# BabyPukeko.net
KiCad netlist of a schematic drawn in Altium Designer
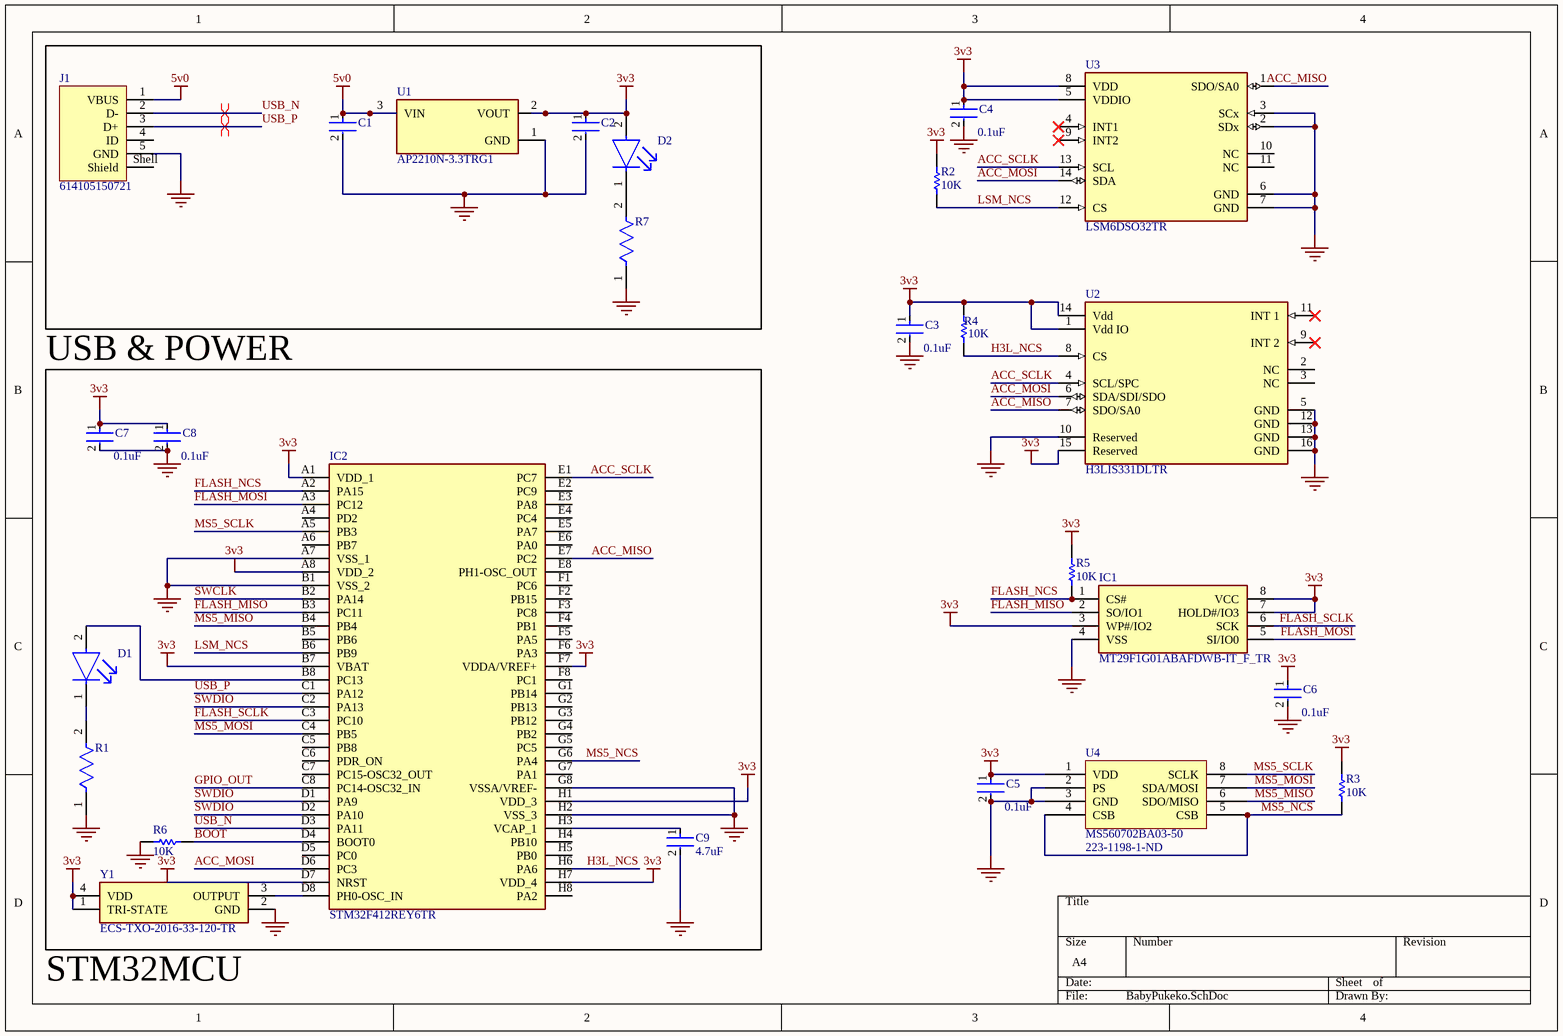
[diagram p0: BabyPukeko.SchDoc]

(export (version "E")
  (design (tool "Eeschema 10.0.6"))
  (components
    (comp (ref "C1")
      (value "C0402C105K8PACTU")
      (footprint "FP-C0402C105K8PACTU-MFG")
      (description "CAP CER 1UF 10V X5R 0402")
      (fields (field (name "VOLTAGE") "10V") (field (name "TOLERANCE") "10%"))
      (libsource (lib "Altium Content Vault") (part "11868f565c42a9108669ba33697ecf6"))
    )
    (comp (ref "C2")
      (value "C0402C105K8PACTU")
      (footprint "FP-C0402C105K8PACTU-MFG")
      (description "CAP CER 1UF 10V X5R 0402")
      (fields (field (name "VOLTAGE") "10V") (field (name "TOLERANCE") "10%"))
      (libsource (lib "Altium Content Vault") (part "11868f565c42a9108669ba33697ecf6"))
    )
    (comp (ref "C3")
      (value "0.1uF")
      (footprint "FP-C0402-BB-MFG")
      (description "CAP CER 0.1UF 10V X5R 0402")
      (fields (field (name "MANUFACTURER") "Kemet") (field (name "TOLERANCE") "0.1"))
      (libsource (lib "Altium Content Vault") (part "b4654b650e69147ec39a6b967a45e02"))
    )
    (comp (ref "C4")
      (value "0.1uF")
      (footprint "FP-C0402-BB-MFG")
      (description "CAP CER 0.1UF 10V X5R 0402")
      (fields (field (name "MANUFACTURER") "Kemet") (field (name "TOLERANCE") "0.1"))
      (libsource (lib "Altium Content Vault") (part "b4654b650e69147ec39a6b967a45e02"))
    )
    (comp (ref "C5")
      (value "0.1uF")
      (footprint "FP-C0402-BB-MFG")
      (description "CAP CER 0.1UF 10V X5R 0402")
      (fields (field (name "MANUFACTURER") "Kemet") (field (name "TOLERANCE") "0.1"))
      (libsource (lib "Altium Content Vault") (part "b4654b650e69147ec39a6b967a45e02"))
    )
    (comp (ref "C6")
      (value "0.1uF")
      (footprint "FP-C0402-BB-MFG")
      (description "CAP CER 0.1UF 10V X5R 0402")
      (fields (field (name "MANUFACTURER") "Kemet") (field (name "TOLERANCE") "0.1"))
      (libsource (lib "Altium Content Vault") (part "b4654b650e69147ec39a6b967a45e02"))
    )
    (comp (ref "C7")
      (value "0.1uF")
      (footprint "FP-C0402-BB-MFG")
      (description "CAP CER 0.1UF 10V X5R 0402")
      (fields (field (name "MANUFACTURER") "Kemet") (field (name "TOLERANCE") "0.1"))
      (libsource (lib "Altium Content Vault") (part "b4654b650e69147ec39a6b967a45e02"))
    )
    (comp (ref "C8")
      (value "0.1uF")
      (footprint "FP-C0402-BB-MFG")
      (description "CAP CER 0.1UF 10V X5R 0402")
      (fields (field (name "MANUFACTURER") "Kemet") (field (name "TOLERANCE") "0.1"))
      (libsource (lib "Altium Content Vault") (part "b4654b650e69147ec39a6b967a45e02"))
    )
    (comp (ref "C9")
      (value "4.7uF")
      (footprint "FP-C1005-050-0_15-MFG")
      (description "CAP CER 4.7UF 10V X5R 0402")
      (fields (field (name "TOLERANCE") "10%"))
      (libsource (lib "Altium Content Vault") (part "b4654b650e69147ec39a6b967a45e02"))
    )
    (comp (ref "D1")
      (value "APHHS1005CGCK")
      (footprint "FP-APHHS1005CGCK-MFG")
      (description "LED GREEN CLEAR CHIP SMD")
      (libsource (lib "Altium Content Vault") (part "8706943c75ba83719d021d2fdc84c58"))
    )
    (comp (ref "D2")
      (value "APHHS1005CGCK")
      (footprint "FP-APHHS1005CGCK-MFG")
      (description "LED GREEN CLEAR CHIP SMD")
      (libsource (lib "Altium Content Vault") (part "8706943c75ba83719d021d2fdc84c58"))
    )
    (comp (ref "IC1")
      (value "MT29F1G01ABAFDWB-IT_F_TR")
      (footprint "SamacSys:SON127P800X600X65-8N")
      (description "Integrated Circuit")
      (fields
        (field (name "MANUFACTURER_PART_NUMBER") "MT29F1G01ABAFDWB-IT:F TR")
        (field (name "MOUSER PART NUMBER") "340-319941-REEL")
      )
      (libsource (lib "*") (part "MT29F1G01ABAFDWB-IT_F_TR"))
    )
    (comp (ref "IC2")
      (value "STM32F412REY6TR")
      (footprint "SamacSys:BGA64C40P8X8_362X365X58")
      (description "Integrated Circuit")
      (fields (field (name "MOUSER PART NUMBER") "511-STM32F412REY6TR"))
      (libsource (lib "*") (part "STM32F412REY6TR"))
    )
    (comp (ref "J1")
      (value "614105150721")
      (footprint "614105150721")
      (libsource (lib "Altium Content Vault") (part "Micro USB 2.0_Type B_Receptacle_1 Port"))
    )
    (comp (ref "R1")
      (value "RC0402FR-071KL")
      (footprint "FP-RC0402-0_4-IPC_A")
      (description "RES 1K OHM 1% 1/16W 0402")
      (fields (field (name "TOLERANCE") "1%"))
      (libsource (lib "Altium Content Vault") (part "1029c3af85768c4190bb7ad29bc67b5"))
    )
    (comp (ref "R2")
      (value "10K")
      (footprint "RESC1005X40X25LL05T10")
      (fields (field (name "PART NUMBER") "RC0402FR-0710KL") (field (name "MANUFACTURER") "Yageo / Phycomp"))
      (libsource (lib "Altium Content Vault") (part "RES"))
    )
    (comp (ref "R3")
      (value "10K")
      (footprint "RESC1005X40X25LL05T10")
      (fields (field (name "PART NUMBER") "RC0402FR-0710KL") (field (name "MANUFACTURER") "Yageo / Phycomp"))
      (libsource (lib "Altium Content Vault") (part "RES"))
    )
    (comp (ref "R4")
      (value "10K")
      (footprint "RESC1005X40X25LL05T10")
      (fields (field (name "PART NUMBER") "RC0402FR-0710KL") (field (name "MANUFACTURER") "Yageo / Phycomp"))
      (libsource (lib "Altium Content Vault") (part "RES"))
    )
    (comp (ref "R5")
      (value "10K")
      (footprint "RESC1005X40X25LL05T10")
      (fields (field (name "PART NUMBER") "RC0402FR-0710KL") (field (name "MANUFACTURER") "Yageo / Phycomp"))
      (libsource (lib "Altium Content Vault") (part "RES"))
    )
    (comp (ref "R6")
      (value "10K")
      (footprint "RESC1005X40X25LL05T10")
      (fields (field (name "PART NUMBER") "RC0402FR-0710KL") (field (name "MANUFACTURER") "Yageo / Phycomp"))
      (libsource (lib "Altium Content Vault") (part "RES"))
    )
    (comp (ref "R7")
      (value "RC0402FR-071KL")
      (footprint "FP-RC0402-0_4-IPC_A")
      (description "RES 1K OHM 1% 1/16W 0402")
      (fields (field (name "TOLERANCE") "1%"))
      (libsource (lib "Altium Content Vault") (part "1029c3af85768c4190bb7ad29bc67b5"))
    )
    (comp (ref "U1")
      (value "AP2210N-3.3TRG1")
      (footprint "FP-SOT23-IPC_C")
      (description "IC REG LINEAR 3.3V 300MA SOT23-3")
      (libsource (lib "Altium Content Vault") (part "bd94623faa3c699494368a50adf163b"))
    )
    (comp (ref "U2")
      (value "H3LIS331DLTR")
      (footprint "FP-TFLGA16-7983231-MFG")
      (description "ACCEL 100-400G I2C/SPI 16TFLGA")
      (fields
        (field (name "OCTOPART") "https://octopart.com/h3lis331dltr-stmicroelectronics-29186499")
        (field (name "MANUFACTURER") "STMicroelectronics")
      )
      (libsource (lib "Altium Content Vault") (part "88bf36ed36dec8c6247366cd2bff627"))
    )
    (comp (ref "U3")
      (value "LSM6DSO32TR")
      (footprint "FP-LGA-14L-DM00249496-MFG")
      (description "INEMO INERTIAL MODULE: 3D ACCELE")
      (libsource (lib "Altium Content Vault") (part "593856c316c551aebc7657d93cdb4f0"))
    )
    (comp (ref "U4")
      (value "MS560702BA03-50")
      (footprint "MS5607")
      (description "Barometric Pressure Sensor I2C/SPI")
      (fields
        (field (name "SUPPLIER PART NUMBER 1") "223-1198-1-ND")
        (field (name "MADE BY") "*")
        (field (name "REVIEWED BY") "Adam Rising")
      )
      (libsource (lib "USCRPL") (part "MS560702BA03-50"))
    )
    (comp (ref "Y1")
      (value "ECS-TXO-2016-33-120-TR")
      (footprint "SamacSys:ECSTXO201633120TR")
      (description "Crystal or Oscillator")
      (fields (field (name "MOUSER PART NUMBER") "520-TXO-2016-33-120T"))
      (libsource (lib "*") (part "ECS-TXO-2016-33-120-TR"))
    )
  )
  (nets
    (net (code "1") (name "/ACC_MISO") (class "Default")
      (node (ref "IC2") (pin "E7") (pinfunction "PC2_E7") (pintype "passive"))
      (node (ref "U2") (pin "7") (pinfunction "SDO/SA0_7") (pintype "bidirectional"))
      (node (ref "U3") (pin "1") (pinfunction "SDO/SA0_1") (pintype "bidirectional"))
    )
    (net (code "2") (name "/ACC_MOSI") (class "Default")
      (node (ref "IC2") (pin "D6") (pinfunction "PC3_D6") (pintype "passive"))
      (node (ref "U2") (pin "6") (pinfunction "SDA/SDI/SDO_6") (pintype "bidirectional"))
      (node (ref "U3") (pin "14") (pinfunction "SDA_14") (pintype "bidirectional"))
    )
    (net (code "3") (name "/ACC_SCLK") (class "Default")
      (node (ref "IC2") (pin "E1") (pinfunction "PC7_E1") (pintype "passive"))
      (node (ref "U2") (pin "4") (pinfunction "SCL/SPC_4") (pintype "input"))
      (node (ref "U3") (pin "13") (pinfunction "SCL_13") (pintype "input"))
    )
    (net (code "4") (name "/BOOT") (class "Default")
      (node (ref "IC2") (pin "D4") (pinfunction "BOOT0_D4") (pintype "passive"))
      (node (ref "R6") (pin "2") (pinfunction "2_2") (pintype "passive"))
    )
    (net (code "5") (name "/FLASH_MISO") (class "Default")
      (node (ref "IC1") (pin "2") (pinfunction "SO/IO1_2") (pintype "passive"))
      (node (ref "IC2") (pin "B3") (pinfunction "PC11_B3") (pintype "passive"))
    )
    (net (code "6") (name "/FLASH_MOSI") (class "Default")
      (node (ref "IC1") (pin "5") (pinfunction "SI/IO0_5") (pintype "passive"))
      (node (ref "IC2") (pin "A3") (pinfunction "PC12_A3") (pintype "passive"))
    )
    (net (code "7") (name "/FLASH_NCS") (class "Default")
      (node (ref "IC1") (pin "1") (pinfunction "CS#_1") (pintype "passive"))
      (node (ref "IC2") (pin "A2") (pinfunction "PA15_A2") (pintype "passive"))
      (node (ref "R5") (pin "2") (pinfunction "2_2") (pintype "passive"))
    )
    (net (code "8") (name "/FLASH_SCLK") (class "Default")
      (node (ref "IC1") (pin "6") (pinfunction "SCK_6") (pintype "passive"))
      (node (ref "IC2") (pin "C3") (pinfunction "PC10_C3") (pintype "passive"))
    )
    (net (code "9") (name "/GPIO_OUT") (class "Default")
      (node (ref "IC2") (pin "C8") (pinfunction "PC14-OSC32_IN_C8") (pintype "passive"))
    )
    (net (code "10") (name "/H3L_NCS") (class "Default")
      (node (ref "IC2") (pin "H6") (pinfunction "PA6_H6") (pintype "passive"))
      (node (ref "R4") (pin "2") (pinfunction "2_2") (pintype "passive"))
      (node (ref "U2") (pin "8") (pinfunction "CS_8") (pintype "input"))
    )
    (net (code "11") (name "/LSM_NCS") (class "Default")
      (node (ref "IC2") (pin "B6") (pinfunction "PB9_B6") (pintype "passive"))
      (node (ref "R2") (pin "2") (pinfunction "2_2") (pintype "passive"))
      (node (ref "U3") (pin "12") (pinfunction "CS_12") (pintype "input"))
    )
    (net (code "12") (name "/MS5_MISO") (class "Default")
      (node (ref "IC2") (pin "B4") (pinfunction "PB4_B4") (pintype "passive"))
      (node (ref "U4") (pin "6") (pinfunction "SDO/MISO_6") (pintype "passive"))
    )
    (net (code "13") (name "/MS5_MOSI") (class "Default")
      (node (ref "IC2") (pin "C4") (pinfunction "PB5_C4") (pintype "passive"))
      (node (ref "U4") (pin "7") (pinfunction "SDA/MOSI_7") (pintype "passive"))
    )
    (net (code "14") (name "/MS5_NCS") (class "Default")
      (node (ref "IC2") (pin "G6") (pinfunction "PA4_G6") (pintype "passive"))
      (node (ref "R3") (pin "2") (pinfunction "2_2") (pintype "passive"))
      (node (ref "U4") (pin "4") (pinfunction "CSB_4") (pintype "passive"))
      (node (ref "U4") (pin "5") (pinfunction "CSB_5") (pintype "passive"))
    )
    (net (code "15") (name "/MS5_SCLK") (class "Default")
      (node (ref "IC2") (pin "A5") (pinfunction "PB3_A5") (pintype "passive"))
      (node (ref "U4") (pin "8") (pinfunction "SCLK_8") (pintype "passive"))
    )
    (net (code "16") (name "/SWCLK") (class "Default")
      (node (ref "IC2") (pin "B2") (pinfunction "PA14_B2") (pintype "passive"))
    )
    (net (code "17") (name "/SWDIO") (class "Default")
      (node (ref "IC2") (pin "C2") (pinfunction "PA13_C2") (pintype "passive"))
      (node (ref "IC2") (pin "D1") (pinfunction "PA9_D1") (pintype "passive"))
      (node (ref "IC2") (pin "D2") (pinfunction "PA10_D2") (pintype "passive"))
    )
    (net (code "18") (name "/USB_N") (class "Default")
      (node (ref "IC2") (pin "D3") (pinfunction "PA11_D3") (pintype "passive"))
      (node (ref "J1") (pin "2") (pinfunction "D-_2") (pintype "passive"))
    )
    (net (code "19") (name "/USB_P") (class "Default")
      (node (ref "IC2") (pin "C1") (pinfunction "PA12_C1") (pintype "passive"))
      (node (ref "J1") (pin "3") (pinfunction "D+_3") (pintype "passive"))
    )
    (net (code "20") (name "3v3") (class "Default")
      (node (ref "C2") (pin "1") (pinfunction "1_1") (pintype "passive"))
      (node (ref "C3") (pin "1") (pinfunction "1_1") (pintype "passive"))
      (node (ref "C4") (pin "1") (pinfunction "1_1") (pintype "passive"))
      (node (ref "C5") (pin "1") (pinfunction "1_1") (pintype "passive"))
      (node (ref "C6") (pin "1") (pinfunction "1_1") (pintype "passive"))
      (node (ref "C7") (pin "1") (pinfunction "1_1") (pintype "passive"))
      (node (ref "C8") (pin "1") (pinfunction "1_1") (pintype "passive"))
      (node (ref "D2") (pin "2") (pinfunction "A_2") (pintype "passive"))
      (node (ref "IC1") (pin "3") (pinfunction "WP#/IO2_3") (pintype "passive"))
      (node (ref "IC1") (pin "7") (pinfunction "HOLD#/IO3_7") (pintype "passive"))
      (node (ref "IC1") (pin "8") (pinfunction "VCC_8") (pintype "passive"))
      (node (ref "IC2") (pin "A1") (pinfunction "VDD_1_A1") (pintype "passive"))
      (node (ref "IC2") (pin "A8") (pinfunction "VDD_2_A8") (pintype "passive"))
      (node (ref "IC2") (pin "B7") (pinfunction "VBAT_B7") (pintype "passive"))
      (node (ref "IC2") (pin "D7") (pinfunction "NRST_D7") (pintype "passive"))
      (node (ref "IC2") (pin "F7") (pinfunction "VDDA/VREF+_F7") (pintype "passive"))
      (node (ref "IC2") (pin "H1") (pinfunction "VDD_3_H1") (pintype "passive"))
      (node (ref "IC2") (pin "H7") (pinfunction "VDD_4_H7") (pintype "passive"))
      (node (ref "R2") (pin "1") (pinfunction "1_1") (pintype "passive"))
      (node (ref "R3") (pin "1") (pinfunction "1_1") (pintype "passive"))
      (node (ref "R4") (pin "1") (pinfunction "1_1") (pintype "passive"))
      (node (ref "R5") (pin "1") (pinfunction "1_1") (pintype "passive"))
      (node (ref "U1") (pin "2") (pinfunction "VOUT_2") (pintype "power_in"))
      (node (ref "U2") (pin "1") (pinfunction "Vdd_IO_1") (pintype "power_in"))
      (node (ref "U2") (pin "14") (pinfunction "Vdd_14") (pintype "power_in"))
      (node (ref "U2") (pin "15") (pinfunction "Reserved_15") (pintype "passive"))
      (node (ref "U3") (pin "5") (pinfunction "VDDIO_5") (pintype "power_in"))
      (node (ref "U3") (pin "8") (pinfunction "VDD_8") (pintype "power_in"))
      (node (ref "U4") (pin "1") (pinfunction "VDD_1") (pintype "passive"))
      (node (ref "Y1") (pin "1") (pinfunction "TRI-STATE_1") (pintype "passive"))
      (node (ref "Y1") (pin "4") (pinfunction "VDD_4") (pintype "passive"))
    )
    (net (code "21") (name "5v0") (class "Default")
      (node (ref "C1") (pin "1") (pinfunction "1_1") (pintype "passive"))
      (node (ref "J1") (pin "1") (pinfunction "VBUS_1") (pintype "passive"))
      (node (ref "U1") (pin "3") (pinfunction "VIN_3") (pintype "power_in"))
    )
    (net (code "22") (name "GND") (class "Default")
      (node (ref "C1") (pin "2") (pinfunction "2_2") (pintype "passive"))
      (node (ref "C2") (pin "2") (pinfunction "2_2") (pintype "passive"))
      (node (ref "C3") (pin "2") (pinfunction "2_2") (pintype "passive"))
      (node (ref "C4") (pin "2") (pinfunction "2_2") (pintype "passive"))
      (node (ref "C5") (pin "2") (pinfunction "2_2") (pintype "passive"))
      (node (ref "C6") (pin "2") (pinfunction "2_2") (pintype "passive"))
      (node (ref "C7") (pin "2") (pinfunction "2_2") (pintype "passive"))
      (node (ref "C8") (pin "2") (pinfunction "2_2") (pintype "passive"))
      (node (ref "C9") (pin "2") (pinfunction "2_2") (pintype "passive"))
      (node (ref "IC1") (pin "4") (pinfunction "VSS_4") (pintype "passive"))
      (node (ref "IC2") (pin "A7") (pinfunction "VSS_1_A7") (pintype "passive"))
      (node (ref "IC2") (pin "B1") (pinfunction "VSS_2_B1") (pintype "passive"))
      (node (ref "IC2") (pin "G8") (pinfunction "VSSA/VREF-_G8") (pintype "passive"))
      (node (ref "IC2") (pin "H2") (pinfunction "VSS_3_H2") (pintype "passive"))
      (node (ref "J1") (pin "5") (pinfunction "GND_5") (pintype "passive"))
      (node (ref "R1") (pin "1") (pinfunction "1_1") (pintype "passive"))
      (node (ref "R6") (pin "1") (pinfunction "1_1") (pintype "passive"))
      (node (ref "R7") (pin "1") (pinfunction "1_1") (pintype "passive"))
      (node (ref "U1") (pin "1") (pinfunction "GND_1") (pintype "power_in"))
      (node (ref "U2") (pin "10") (pinfunction "Reserved_10") (pintype "passive"))
      (node (ref "U2") (pin "12") (pinfunction "GND_12") (pintype "power_in"))
      (node (ref "U2") (pin "13") (pinfunction "GND_13") (pintype "power_in"))
      (node (ref "U2") (pin "16") (pinfunction "GND_16") (pintype "power_in"))
      (node (ref "U2") (pin "5") (pinfunction "GND_5") (pintype "power_in"))
      (node (ref "U3") (pin "2") (pinfunction "SDx_2") (pintype "bidirectional"))
      (node (ref "U3") (pin "3") (pinfunction "SCx_3") (pintype "input"))
      (node (ref "U3") (pin "6") (pinfunction "GND_6") (pintype "power_in"))
      (node (ref "U3") (pin "7") (pinfunction "GND_7") (pintype "power_in"))
      (node (ref "U4") (pin "2") (pinfunction "PS_2") (pintype "passive"))
      (node (ref "U4") (pin "3") (pinfunction "GND_3") (pintype "passive"))
      (node (ref "Y1") (pin "2") (pinfunction "GND_2") (pintype "passive"))
    )
    (net (code "23") (name "Net-(D1-A)") (class "Default")
      (node (ref "D1") (pin "2") (pinfunction "A_2") (pintype "passive"))
      (node (ref "IC2") (pin "B8") (pinfunction "PC13_B8") (pintype "passive"))
    )
    (net (code "24") (name "Net-(D1-C)") (class "Default")
      (node (ref "D1") (pin "1") (pinfunction "C_1") (pintype "passive"))
      (node (ref "R1") (pin "2") (pinfunction "2_2") (pintype "passive"))
    )
    (net (code "25") (name "Net-(D2-C)") (class "Default")
      (node (ref "D2") (pin "1") (pinfunction "C_1") (pintype "passive"))
      (node (ref "R7") (pin "2") (pinfunction "2_2") (pintype "passive"))
    )
    (net (code "26") (name "Net-(IC2-PH0-OSC_IN)") (class "Default")
      (node (ref "IC2") (pin "D8") (pinfunction "PH0-OSC_IN_D8") (pintype "passive"))
      (node (ref "Y1") (pin "3") (pinfunction "OUTPUT_3") (pintype "passive"))
    )
    (net (code "27") (name "Net-(IC2-VCAP_1)") (class "Default")
      (node (ref "C9") (pin "1") (pinfunction "1_1") (pintype "passive"))
      (node (ref "IC2") (pin "H3") (pinfunction "VCAP_1_H3") (pintype "passive"))
    )
    (net (code "28") (name "unconnected-(IC2-PA0-PadE6)") (class "Default")
      (node (ref "IC2") (pin "E6") (pinfunction "PA0_E6") (pintype "passive"))
    )
    (net (code "29") (name "unconnected-(IC2-PA1-PadG7)") (class "Default")
      (node (ref "IC2") (pin "G7") (pinfunction "PA1_G7") (pintype "passive"))
    )
    (net (code "30") (name "unconnected-(IC2-PA2-PadH8)") (class "Default")
      (node (ref "IC2") (pin "H8") (pinfunction "PA2_H8") (pintype "passive"))
    )
    (net (code "31") (name "unconnected-(IC2-PA3-PadF6)") (class "Default")
      (node (ref "IC2") (pin "F6") (pinfunction "PA3_F6") (pintype "passive"))
    )
    (net (code "32") (name "unconnected-(IC2-PA5-PadF5)") (class "Default")
      (node (ref "IC2") (pin "F5") (pinfunction "PA5_F5") (pintype "passive"))
    )
    (net (code "33") (name "unconnected-(IC2-PA7-PadE5)") (class "Default")
      (node (ref "IC2") (pin "E5") (pinfunction "PA7_E5") (pintype "passive"))
    )
    (net (code "34") (name "unconnected-(IC2-PA8-PadE3)") (class "Default")
      (node (ref "IC2") (pin "E3") (pinfunction "PA8_E3") (pintype "passive"))
    )
    (net (code "35") (name "unconnected-(IC2-PB0-PadH5)") (class "Default")
      (node (ref "IC2") (pin "H5") (pinfunction "PB0_H5") (pintype "passive"))
    )
    (net (code "36") (name "unconnected-(IC2-PB1-PadF4)") (class "Default")
      (node (ref "IC2") (pin "F4") (pinfunction "PB1_F4") (pintype "passive"))
    )
    (net (code "37") (name "unconnected-(IC2-PB2-PadG4)") (class "Default")
      (node (ref "IC2") (pin "G4") (pinfunction "PB2_G4") (pintype "passive"))
    )
    (net (code "38") (name "unconnected-(IC2-PB6-PadB5)") (class "Default")
      (node (ref "IC2") (pin "B5") (pinfunction "PB6_B5") (pintype "passive"))
    )
    (net (code "39") (name "unconnected-(IC2-PB7-PadA6)") (class "Default")
      (node (ref "IC2") (pin "A6") (pinfunction "PB7_A6") (pintype "passive"))
    )
    (net (code "40") (name "unconnected-(IC2-PB8-PadC5)") (class "Default")
      (node (ref "IC2") (pin "C5") (pinfunction "PB8_C5") (pintype "passive"))
    )
    (net (code "41") (name "unconnected-(IC2-PB10-PadH4)") (class "Default")
      (node (ref "IC2") (pin "H4") (pinfunction "PB10_H4") (pintype "passive"))
    )
    (net (code "42") (name "unconnected-(IC2-PB12-PadG3)") (class "Default")
      (node (ref "IC2") (pin "G3") (pinfunction "PB12_G3") (pintype "passive"))
    )
    (net (code "43") (name "unconnected-(IC2-PB13-PadG2)") (class "Default")
      (node (ref "IC2") (pin "G2") (pinfunction "PB13_G2") (pintype "passive"))
    )
    (net (code "44") (name "unconnected-(IC2-PB14-PadG1)") (class "Default")
      (node (ref "IC2") (pin "G1") (pinfunction "PB14_G1") (pintype "passive"))
    )
    (net (code "45") (name "unconnected-(IC2-PB15-PadF2)") (class "Default")
      (node (ref "IC2") (pin "F2") (pinfunction "PB15_F2") (pintype "passive"))
    )
    (net (code "46") (name "unconnected-(IC2-PC0-PadD5)") (class "Default")
      (node (ref "IC2") (pin "D5") (pinfunction "PC0_D5") (pintype "passive"))
    )
    (net (code "47") (name "unconnected-(IC2-PC1-PadF8)") (class "Default")
      (node (ref "IC2") (pin "F8") (pinfunction "PC1_F8") (pintype "passive"))
    )
    (net (code "48") (name "unconnected-(IC2-PC4-PadE4)") (class "Default")
      (node (ref "IC2") (pin "E4") (pinfunction "PC4_E4") (pintype "passive"))
    )
    (net (code "49") (name "unconnected-(IC2-PC5-PadG5)") (class "Default")
      (node (ref "IC2") (pin "G5") (pinfunction "PC5_G5") (pintype "passive"))
    )
    (net (code "50") (name "unconnected-(IC2-PC6-PadF1)") (class "Default")
      (node (ref "IC2") (pin "F1") (pinfunction "PC6_F1") (pintype "passive"))
    )
    (net (code "51") (name "unconnected-(IC2-PC8-PadF3)") (class "Default")
      (node (ref "IC2") (pin "F3") (pinfunction "PC8_F3") (pintype "passive"))
    )
    (net (code "52") (name "unconnected-(IC2-PC9-PadE2)") (class "Default")
      (node (ref "IC2") (pin "E2") (pinfunction "PC9_E2") (pintype "passive"))
    )
    (net (code "53") (name "unconnected-(IC2-PC15-OSC32_OUT-PadC7)") (class "Default")
      (node (ref "IC2") (pin "C7") (pinfunction "PC15-OSC32_OUT_C7") (pintype "passive"))
    )
    (net (code "54") (name "unconnected-(IC2-PD2-PadA4)") (class "Default")
      (node (ref "IC2") (pin "A4") (pinfunction "PD2_A4") (pintype "passive"))
    )
    (net (code "55") (name "unconnected-(IC2-PDR_ON-PadC6)") (class "Default")
      (node (ref "IC2") (pin "C6") (pinfunction "PDR_ON_C6") (pintype "passive"))
    )
    (net (code "56") (name "unconnected-(IC2-PH1-OSC_OUT-PadE8)") (class "Default")
      (node (ref "IC2") (pin "E8") (pinfunction "PH1-OSC_OUT_E8") (pintype "passive"))
    )
    (net (code "57") (name "unconnected-(J1-ID-Pad4)") (class "Default")
      (node (ref "J1") (pin "4") (pinfunction "ID_4") (pintype "passive"))
    )
    (net (code "58") (name "unconnected-(J1-Shield-PadShell)") (class "Default")
      (node (ref "J1") (pin "Shell") (pinfunction "Shield_Shell") (pintype "passive"))
    )
    (net (code "59") (name "unconnected-(U2-INT_1-Pad11)") (class "Default")
      (node (ref "U2") (pin "11") (pinfunction "INT_1_11") (pintype "input+no_connect"))
    )
    (net (code "60") (name "unconnected-(U2-INT_2-Pad9)") (class "Default")
      (node (ref "U2") (pin "9") (pinfunction "INT_2_9") (pintype "input+no_connect"))
    )
    (net (code "61") (name "unconnected-(U2-NC-Pad2)") (class "Default")
      (node (ref "U2") (pin "2") (pinfunction "NC_2") (pintype "passive"))
    )
    (net (code "62") (name "unconnected-(U2-NC-Pad3)") (class "Default")
      (node (ref "U2") (pin "3") (pinfunction "NC_3") (pintype "passive"))
    )
    (net (code "63") (name "unconnected-(U3-INT1-Pad4)") (class "Default")
      (node (ref "U3") (pin "4") (pinfunction "INT1_4") (pintype "input+no_connect"))
    )
    (net (code "64") (name "unconnected-(U3-INT2-Pad9)") (class "Default")
      (node (ref "U3") (pin "9") (pinfunction "INT2_9") (pintype "input+no_connect"))
    )
    (net (code "65") (name "unconnected-(U3-NC-Pad10)") (class "Default")
      (node (ref "U3") (pin "10") (pinfunction "NC_10") (pintype "passive"))
    )
    (net (code "66") (name "unconnected-(U3-NC-Pad11)") (class "Default")
      (node (ref "U3") (pin "11") (pinfunction "NC_11") (pintype "passive"))
    )
  )
)
